# USB_Power_Board.net
KiCad netlist of a schematic drawn in EAGLE
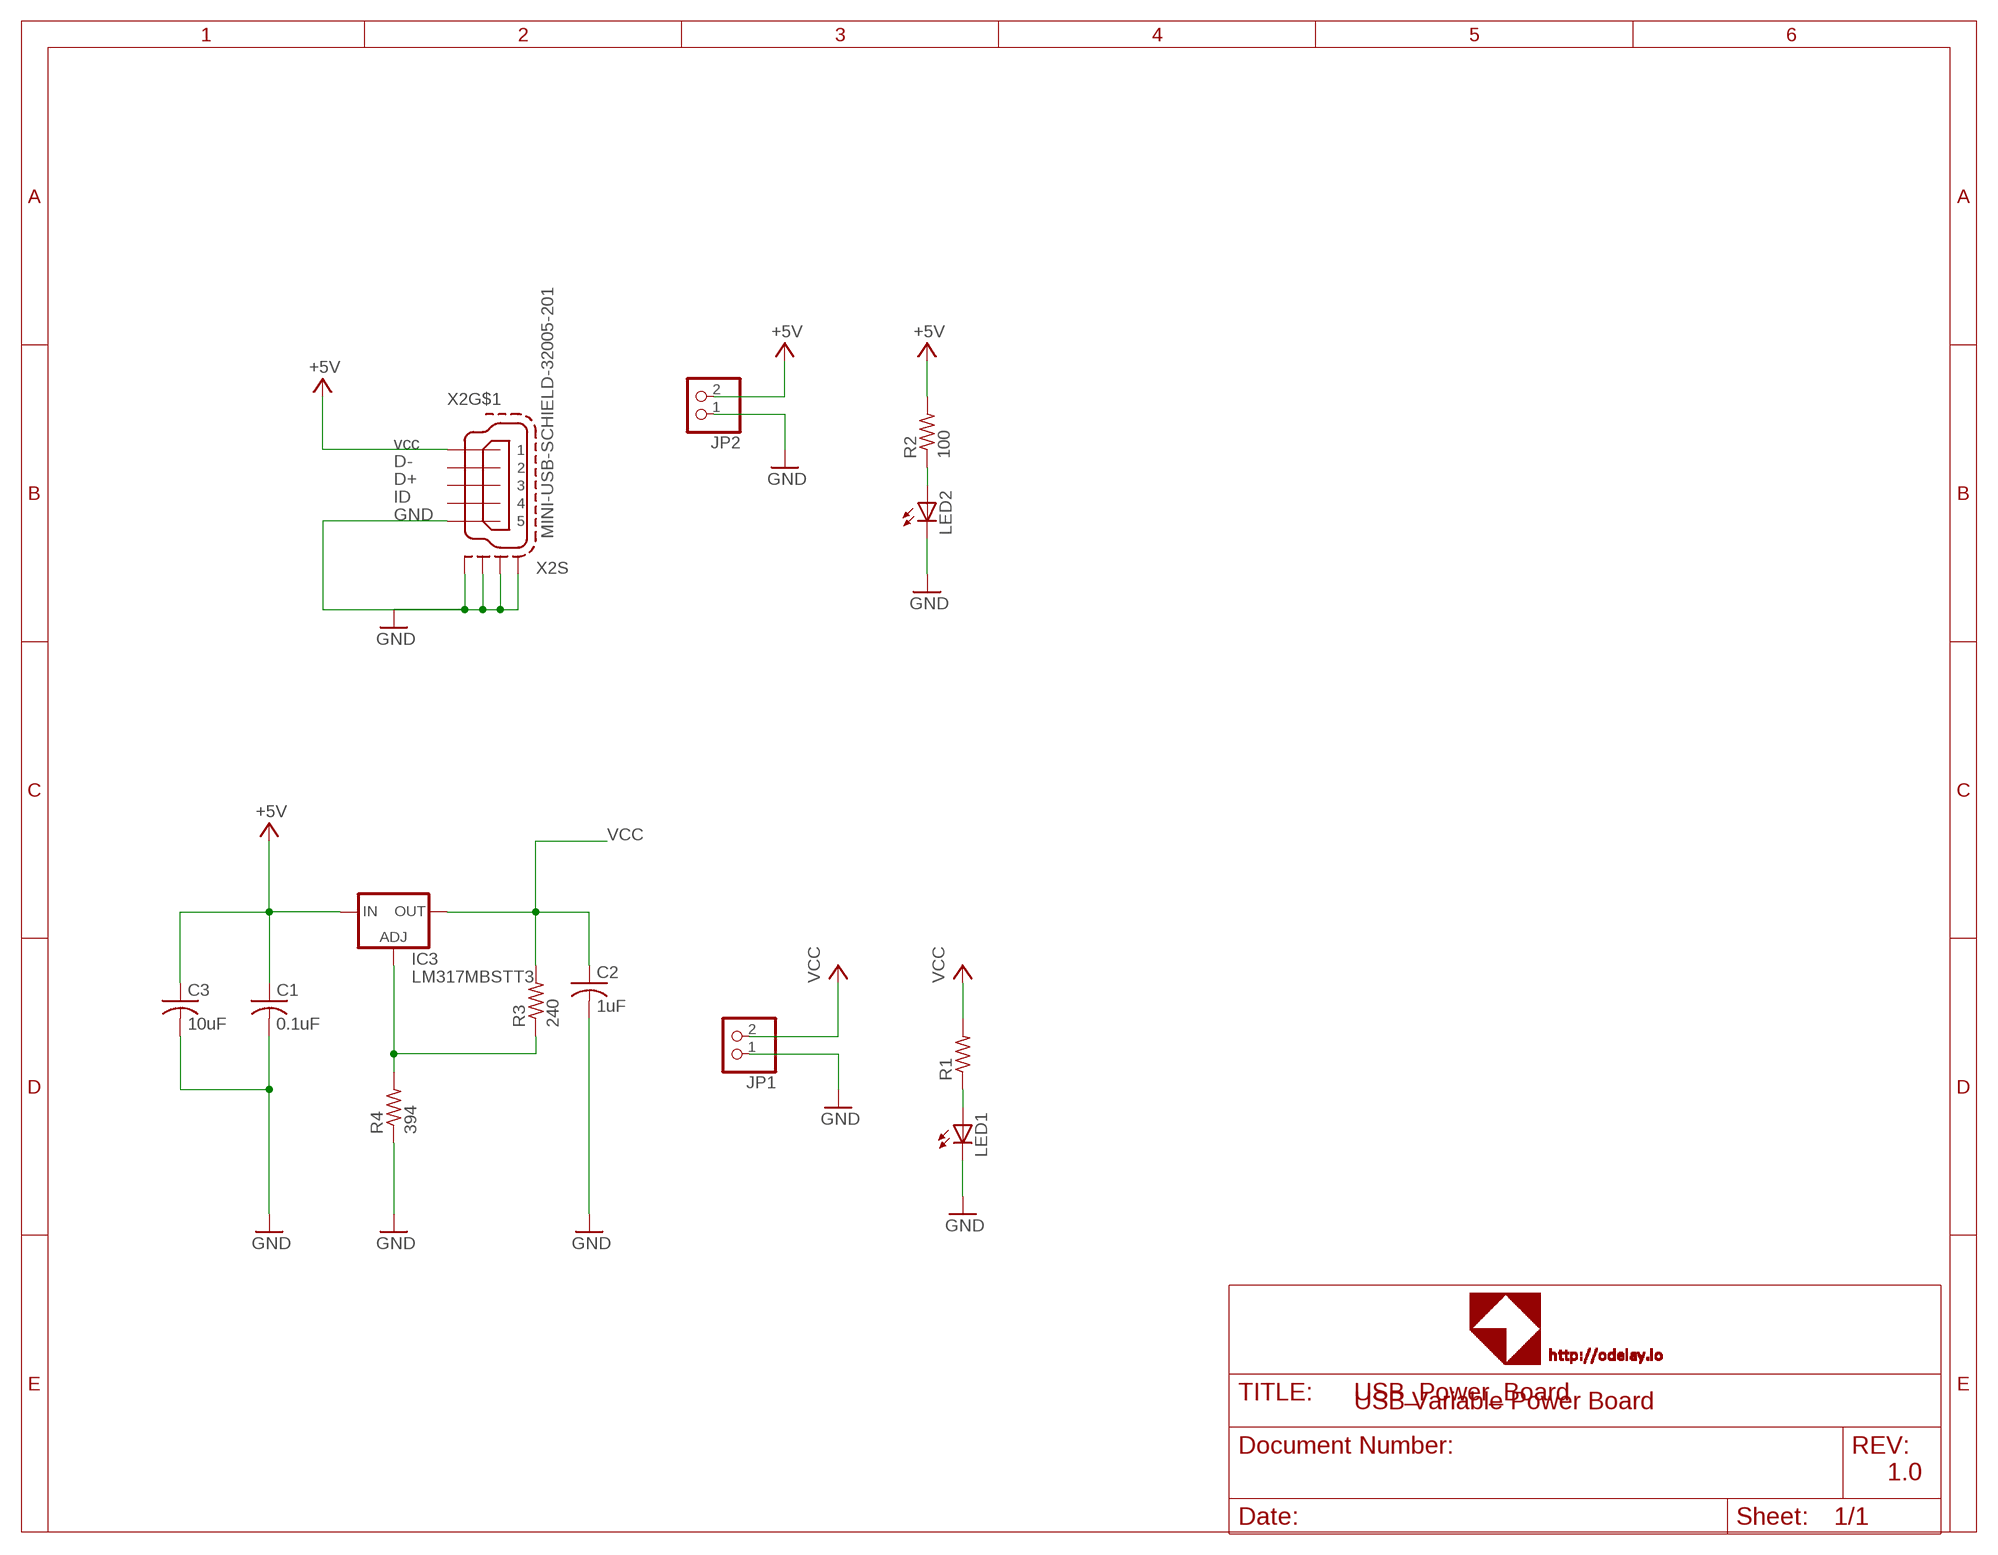
[diagram p0: schematic, sheet 1]

(export (version "E")
  (design (tool "Eeschema 10.0.6"))
  (components
    (comp (ref "C1")
      (value "0.1uF")
      (footprint "eagle-import:C0402")
      (libsource (lib "eagle-import") (part "C-USC0402"))
    )
    (comp (ref "C2")
      (value "1uF")
      (footprint "eagle-import:C0402")
      (libsource (lib "eagle-import") (part "C-USC0402"))
    )
    (comp (ref "C3")
      (value "10uF")
      (footprint "eagle-import:C0603")
      (libsource (lib "eagle-import") (part "C-USC0603"))
    )
    (comp (ref "IC3")
      (value "LM317MBSTT3")
      (footprint "eagle-import:SOT223")
      (libsource (lib "eagle-import") (part "LM317?MBSTT3"))
    )
    (comp (ref "JP1")
      (value "PINHD-1X2")
      (footprint "eagle-import:1X02")
      (libsource (lib "eagle-import") (part "PINHD-1X2"))
    )
    (comp (ref "JP2")
      (value "PINHD-1X2")
      (footprint "eagle-import:1X02")
      (libsource (lib "eagle-import") (part "PINHD-1X2"))
    )
    (comp (ref "LED1")
      (value "LEDCHIP-LED0603")
      (footprint "eagle-import:CHIP-LED0603")
      (libsource (lib "eagle-import") (part "LEDCHIP-LED0603"))
    )
    (comp (ref "LED2")
      (value "LEDCHIP-LED0603")
      (footprint "eagle-import:CHIP-LED0603")
      (libsource (lib "eagle-import") (part "LEDCHIP-LED0603"))
    )
    (comp (ref "R1")
      (value "R-US_R0402")
      (footprint "eagle-import:R0402")
      (libsource (lib "eagle-import") (part "R-US_R0402"))
    )
    (comp (ref "R2")
      (value "100")
      (footprint "eagle-import:R0402")
      (libsource (lib "eagle-import") (part "R-US_R0402"))
    )
    (comp (ref "R3")
      (value "240")
      (footprint "eagle-import:R0805")
      (libsource (lib "eagle-import") (part "R-US_R0805"))
    )
    (comp (ref "R4")
      (value "394")
      (footprint "eagle-import:R0805")
      (libsource (lib "eagle-import") (part "R-US_R0805"))
    )
    (comp (ref "X2")
      (value "MINI-USB-SCHIELD-32005-201")
      (footprint "eagle-import:32005-201")
      (libsource (lib "eagle-import") (part "MINI-USB-SCHIELD-32005-201"))
    )
  )
  (nets
    (net (code "1") (name "+5V") (class "Default")
      (node (ref "C1") (pin "1") (pinfunction "1_1") (pintype "passive"))
      (node (ref "C3") (pin "1") (pinfunction "1_1") (pintype "passive"))
      (node (ref "IC3") (pin "3") (pinfunction "IN_3") (pintype "input"))
      (node (ref "JP2") (pin "2") (pinfunction "2_2") (pintype "passive"))
      (node (ref "R2") (pin "2") (pinfunction "2_2") (pintype "passive"))
      (node (ref "X2") (pin "1") (pinfunction "1_1") (pintype "passive"))
    )
    (net (code "2") (name "GND") (class "Default")
      (node (ref "C1") (pin "2") (pinfunction "2_2") (pintype "passive"))
      (node (ref "C2") (pin "2") (pinfunction "2_2") (pintype "passive"))
      (node (ref "C3") (pin "2") (pinfunction "2_2") (pintype "passive"))
      (node (ref "JP1") (pin "1") (pinfunction "1_1") (pintype "passive"))
      (node (ref "JP2") (pin "1") (pinfunction "1_1") (pintype "passive"))
      (node (ref "LED1") (pin "C") (pinfunction "C_C") (pintype "passive"))
      (node (ref "LED2") (pin "C") (pinfunction "C_C") (pintype "passive"))
      (node (ref "R4") (pin "1") (pinfunction "1_1") (pintype "passive"))
      (node (ref "X2") (pin "5") (pinfunction "5_5") (pintype "passive"))
      (node (ref "X2") (pin "M1") (pinfunction "S1_M1") (pintype "passive"))
      (node (ref "X2") (pin "M2") (pinfunction "S2_M2") (pintype "passive"))
      (node (ref "X2") (pin "M3") (pinfunction "S3_M3") (pintype "passive"))
      (node (ref "X2") (pin "M4") (pinfunction "S4_M4") (pintype "passive"))
    )
    (net (code "3") (name "Net-(IC3-ADJ)") (class "Default")
      (node (ref "IC3") (pin "1") (pinfunction "ADJ_1") (pintype "input"))
      (node (ref "R3") (pin "1") (pinfunction "1_1") (pintype "passive"))
      (node (ref "R4") (pin "2") (pinfunction "2_2") (pintype "passive"))
    )
    (net (code "4") (name "Net-(LED1-PadA)") (class "Default")
      (node (ref "LED1") (pin "A") (pinfunction "A_A") (pintype "passive"))
      (node (ref "R1") (pin "1") (pinfunction "1_1") (pintype "passive"))
    )
    (net (code "5") (name "Net-(LED2-PadA)") (class "Default")
      (node (ref "LED2") (pin "A") (pinfunction "A_A") (pintype "passive"))
      (node (ref "R2") (pin "1") (pinfunction "1_1") (pintype "passive"))
    )
    (net (code "6") (name "VCC") (class "Default")
      (node (ref "C2") (pin "1") (pinfunction "1_1") (pintype "passive"))
      (node (ref "IC3") (pin "4") (pinfunction "OUT_4") (pintype "passive"))
      (node (ref "JP1") (pin "2") (pinfunction "2_2") (pintype "passive"))
      (node (ref "R1") (pin "2") (pinfunction "2_2") (pintype "passive"))
      (node (ref "R3") (pin "2") (pinfunction "2_2") (pintype "passive"))
    )
    (net (code "7") (name "unconnected-(X2-Pad2)") (class "Default")
      (node (ref "X2") (pin "2") (pinfunction "2_2") (pintype "passive"))
    )
    (net (code "8") (name "unconnected-(X2-Pad3)") (class "Default")
      (node (ref "X2") (pin "3") (pinfunction "3_3") (pintype "passive"))
    )
    (net (code "9") (name "unconnected-(X2-Pad4)") (class "Default")
      (node (ref "X2") (pin "4") (pinfunction "4_4") (pintype "passive"))
    )
  )
)
